# Power.net
KiCad netlist of a schematic drawn in Altium Designer
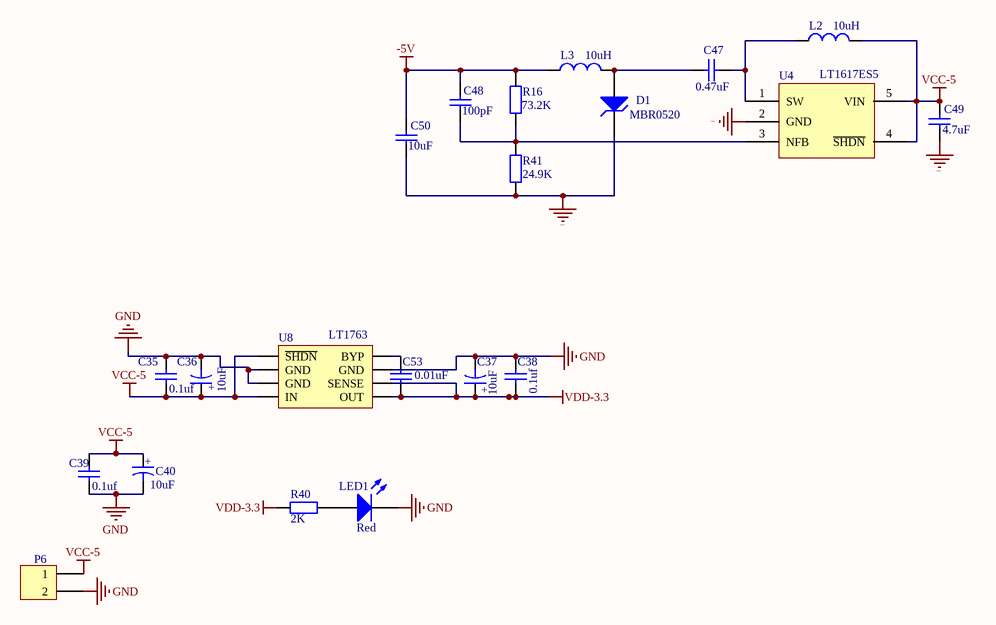
[diagram p0: Power.SchDoc]

(export (version "E")
  (design (tool "Eeschema 10.0.6"))
  (components
    (comp (ref "C35")
      (value "0.1uf")
      (footprint "0805")
      (fields (field (name "Comment") "Capacitor-0805"))
      (libsource (lib "集成库—大岐") (part "Capacitor-0805"))
    )
    (comp (ref "C36")
      (value "10uF")
      (footprint "钽电容1206（A3216）")
      (fields (field (name "ALTIUM_UNNAMED_1") "+") (field (name "Comment") "电解电容"))
      (libsource (lib "集成库—大岐") (part "电解电容"))
    )
    (comp (ref "C37")
      (value "10uF")
      (footprint "钽电容1206（A3216）")
      (fields (field (name "ALTIUM_UNNAMED_1") "+") (field (name "Comment") "电解电容"))
      (libsource (lib "集成库—大岐") (part "电解电容"))
    )
    (comp (ref "C38")
      (value "0.1uf")
      (footprint "0805")
      (fields (field (name "Comment") "Capacitor-0805"))
      (libsource (lib "集成库—大岐") (part "Capacitor-0805"))
    )
    (comp (ref "C39")
      (value "0.1uf")
      (footprint "0805")
      (fields (field (name "Comment") "Capacitor-0805"))
      (libsource (lib "集成库—大岐") (part "Capacitor-0805"))
    )
    (comp (ref "C40")
      (value "10uF")
      (footprint "钽电容1206（A3216）")
      (fields (field (name "ALTIUM_UNNAMED_1") "+") (field (name "Comment") "电解电容"))
      (libsource (lib "集成库—大岐") (part "电解电容"))
    )
    (comp (ref "C47")
      (value "0.47uF")
      (footprint "0805")
      (fields (field (name "Comment") "Capacitor-0805"))
      (libsource (lib "集成库—大岐") (part "Capacitor-0805"))
    )
    (comp (ref "C48")
      (value "100pF")
      (footprint "0603")
      (fields (field (name "Comment") "Capacitor-0603"))
      (libsource (lib "原理图库") (part "Capacitor-0603"))
    )
    (comp (ref "C49")
      (value "4.7uF")
      (footprint "0805")
      (fields (field (name "Comment") "Capacitor-0805"))
      (libsource (lib "集成库—大岐") (part "Capacitor-0805"))
    )
    (comp (ref "C50")
      (value "10uF")
      (footprint "0805")
      (fields (field (name "Comment") "Capacitor-0805"))
      (libsource (lib "集成库—大岐") (part "Capacitor-0805"))
    )
    (comp (ref "C53")
      (value "0.01uF")
      (footprint "0603")
      (fields (field (name "Comment") "Capacitor-0805"))
      (libsource (lib "集成库—大岐") (part "Capacitor-0805"))
    )
    (comp (ref "D1")
      (value "SMBJ20A")
      (footprint "SMBJ20A")
      (fields (field (name "NAME") "MBR0520"))
      (libsource (lib "原理图库") (part "SMBJ20A"))
    )
    (comp (ref "L2")
      (value "10uH")
      (footprint "0805")
      (fields (field (name "Comment") "Inductor"))
      (libsource (lib "原理图库") (part "Inductor"))
    )
    (comp (ref "L3")
      (value "10uH")
      (footprint "0805")
      (fields (field (name "Comment") "Inductor"))
      (libsource (lib "原理图库") (part "Inductor"))
    )
    (comp (ref "LED1")
      (value "LED")
      (footprint "LED-0805")
      (fields (field (name "COLOR") "Red"))
      (libsource (lib "原理图库") (part "LED"))
    )
    (comp (ref "P6") (value "端子") (footprint "2MM接线端子") (libsource (lib "原理图库") (part "端子")))
    (comp (ref "R16")
      (value "73.2K")
      (footprint "0603")
      (fields (field (name "Comment") "Resistor-0603"))
      (libsource (lib "") (part "Resistor-0603_1"))
    )
    (comp (ref "R40")
      (value "2K")
      (footprint "0603")
      (fields (field (name "Comment") "Resistor-0603"))
      (libsource (lib "原理图库") (part "Resistor-0603"))
    )
    (comp (ref "R41")
      (value "24.9K")
      (footprint "0603")
      (fields (field (name "Comment") "Resistor-0603"))
      (libsource (lib "") (part "Resistor-0603_1"))
    )
    (comp (ref "U4") (value "LT1617ES5") (footprint "SOT23-5") (libsource (lib "原理图库") (part "LT1617ES5")))
    (comp (ref "U8") (value "LT1763") (footprint "LT1963") (libsource (lib "原理图库") (part "LT1763")))
  )
  (nets
    (net (code "1") (name "-5V") (class "Default")
      (node (ref "C48") (pin "2") (pinfunction "2_2") (pintype "passive"))
      (node (ref "C50") (pin "2") (pinfunction "2_2") (pintype "passive"))
      (node (ref "L3") (pin "1") (pinfunction "1_1") (pintype "passive"))
      (node (ref "R16") (pin "2") (pinfunction "2_2") (pintype "passive"))
    )
    (net (code "2") (name "GND") (class "Default")
      (node (ref "C35") (pin "2") (pinfunction "2_2") (pintype "passive"))
      (node (ref "C36") (pin "1") (pinfunction "1_1") (pintype "passive"))
      (node (ref "C37") (pin "1") (pinfunction "1_1") (pintype "passive"))
      (node (ref "C38") (pin "2") (pinfunction "2_2") (pintype "passive"))
      (node (ref "C39") (pin "1") (pinfunction "1_1") (pintype "passive"))
      (node (ref "C40") (pin "1") (pinfunction "1_1") (pintype "passive"))
      (node (ref "C49") (pin "1") (pinfunction "1_1") (pintype "passive"))
      (node (ref "C50") (pin "1") (pinfunction "1_1") (pintype "passive"))
      (node (ref "D1") (pin "2") (pinfunction "K_2") (pintype "passive"))
      (node (ref "LED1") (pin "2") (pinfunction "2_2") (pintype "passive"))
      (node (ref "P6") (pin "2") (pinfunction "2_2") (pintype "passive"))
      (node (ref "R41") (pin "1") (pinfunction "1_1") (pintype "passive"))
      (node (ref "U4") (pin "2") (pinfunction "GND_2") (pintype "passive"))
      (node (ref "U8") (pin "3") (pinfunction "GND_3") (pintype "passive"))
      (node (ref "U8") (pin "6") (pinfunction "GND_6") (pintype "passive"))
      (node (ref "U8") (pin "7") (pinfunction "GND_7") (pintype "passive"))
    )
    (net (code "3") (name "Net-(D1-A)") (class "Default")
      (node (ref "C47") (pin "2") (pinfunction "2_2") (pintype "passive"))
      (node (ref "D1") (pin "1") (pinfunction "A_1") (pintype "passive"))
      (node (ref "L3") (pin "2") (pinfunction "2_2") (pintype "passive"))
    )
    (net (code "4") (name "Net-(LED1-A)") (class "Default")
      (node (ref "LED1") (pin "1") (pinfunction "A_1") (pintype "passive"))
      (node (ref "R40") (pin "1") (pinfunction "1_1") (pintype "passive"))
    )
    (net (code "5") (name "Net-(U4-NFB)") (class "Default")
      (node (ref "C48") (pin "1") (pinfunction "1_1") (pintype "passive"))
      (node (ref "R16") (pin "1") (pinfunction "1_1") (pintype "passive"))
      (node (ref "R41") (pin "2") (pinfunction "2_2") (pintype "passive"))
      (node (ref "U4") (pin "3") (pinfunction "NFB_3") (pintype "passive"))
    )
    (net (code "6") (name "Net-(U4-SW)") (class "Default")
      (node (ref "C47") (pin "1") (pinfunction "1_1") (pintype "passive"))
      (node (ref "L2") (pin "1") (pinfunction "1_1") (pintype "passive"))
      (node (ref "U4") (pin "1") (pinfunction "SW_1") (pintype "passive"))
    )
    (net (code "7") (name "Net-(U8-BYP)") (class "Default")
      (node (ref "C53") (pin "2") (pinfunction "2_2") (pintype "passive"))
      (node (ref "U8") (pin "4") (pinfunction "BYP_4") (pintype "passive"))
    )
    (net (code "8") (name "VCC-5") (class "Default")
      (node (ref "C35") (pin "1") (pinfunction "1_1") (pintype "passive"))
      (node (ref "C36") (pin "2") (pinfunction "2_2") (pintype "passive"))
      (node (ref "C39") (pin "2") (pinfunction "2_2") (pintype "passive"))
      (node (ref "C40") (pin "2") (pinfunction "2_2") (pintype "passive"))
      (node (ref "C49") (pin "2") (pinfunction "2_2") (pintype "passive"))
      (node (ref "L2") (pin "2") (pinfunction "2_2") (pintype "passive"))
      (node (ref "P6") (pin "1") (pinfunction "1_1") (pintype "passive"))
      (node (ref "U4") (pin "4") (pinfunction "~{SHDN}_4") (pintype "passive"))
      (node (ref "U4") (pin "5") (pinfunction "VIN_5") (pintype "passive"))
      (node (ref "U8") (pin "5") (pinfunction "~{SHDN}_5") (pintype "passive"))
      (node (ref "U8") (pin "8") (pinfunction "IN_8") (pintype "passive"))
    )
    (net (code "9") (name "VDD-3.3") (class "Default")
      (node (ref "C37") (pin "2") (pinfunction "2_2") (pintype "passive"))
      (node (ref "C38") (pin "1") (pinfunction "1_1") (pintype "passive"))
      (node (ref "C53") (pin "1") (pinfunction "1_1") (pintype "passive"))
      (node (ref "R40") (pin "2") (pinfunction "2_2") (pintype "passive"))
      (node (ref "U8") (pin "1") (pinfunction "OUT_1") (pintype "passive"))
      (node (ref "U8") (pin "2") (pinfunction "SENSE_2") (pintype "passive"))
    )
  )
)
